# NFC_BusinessCard.net
KiCad netlist of a schematic drawn in EAGLE
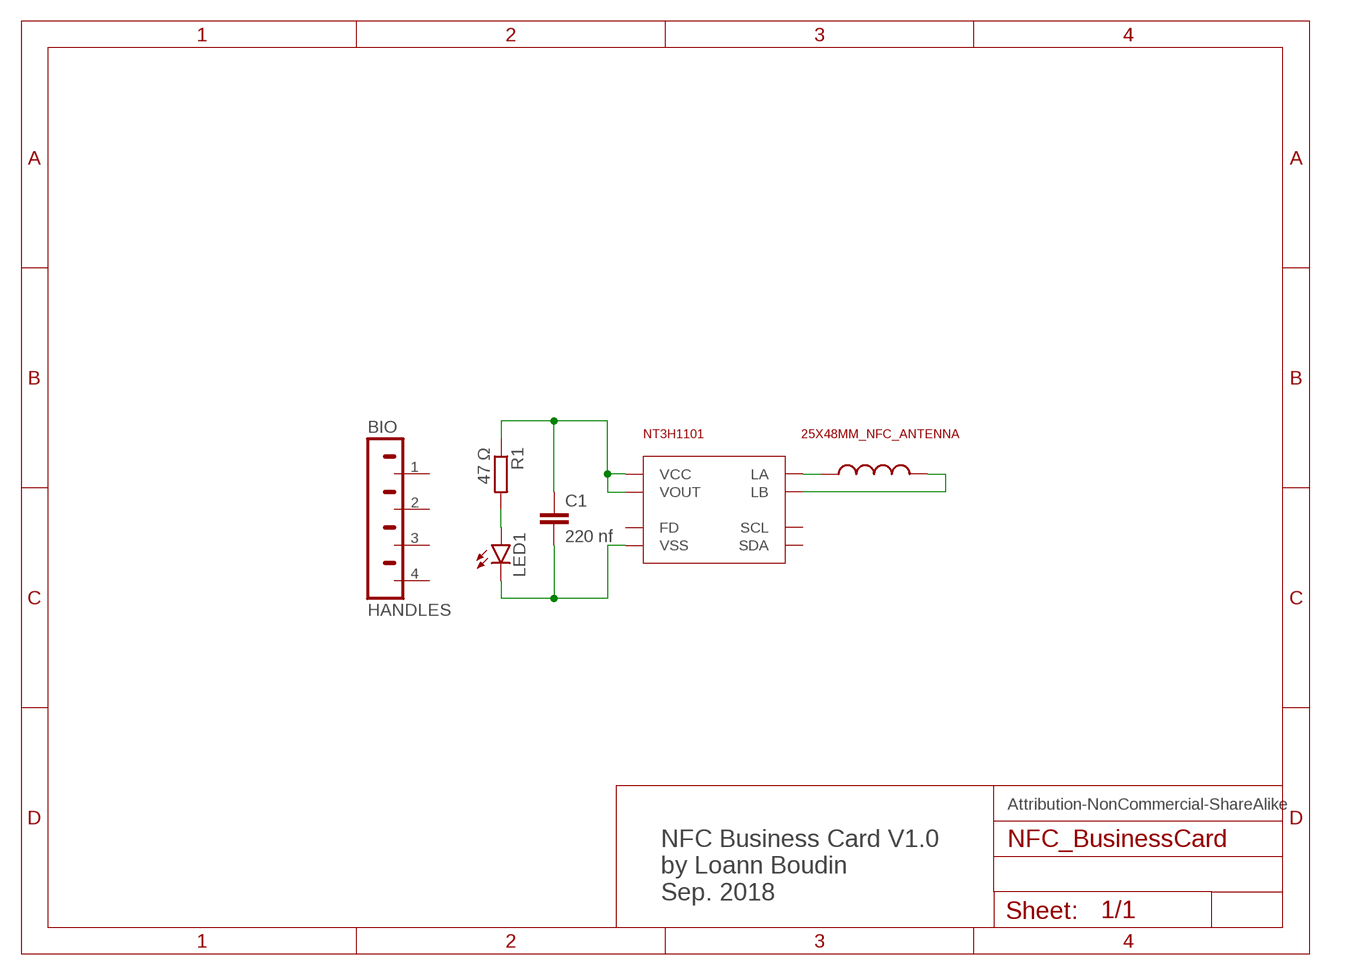
[diagram p0: schematic, sheet 1]

(export (version "E")
  (design (tool "Eeschema 10.0.6"))
  (components
    (comp (ref "ANT")
      (value "25X48MM_NFC_ANTENNA")
      (footprint "eagle-import:25X48MM_NFC")
      (libsource (lib "eagle-import") (part "25X48MM_NFC_ANTENNA"))
    )
    (comp (ref "BIO")
      (value "HANDLES")
      (footprint "eagle-import:MA08-1")
      (libsource (lib "eagle-import") (part "HANDLES"))
    )
    (comp (ref "C1")
      (value "220 nf")
      (footprint "eagle-import:C0603")
      (libsource (lib "eagle-import") (part "C-EUC0603"))
    )
    (comp (ref "LED1")
      (value "LEDSML0805")
      (footprint "eagle-import:SML0805")
      (libsource (lib "eagle-import") (part "LEDSML0805"))
    )
    (comp (ref "NT3H1101")
      (value "NT3H")
      (footprint "eagle-import:XQFN8")
      (libsource (lib "eagle-import") (part "NT3H"))
    )
    (comp (ref "R1")
      (value "47 Ω")
      (footprint "eagle-import:R0603")
      (libsource (lib "eagle-import") (part "R-EU_R0603"))
    )
  )
  (nets
    (net (code "1") (name "Net-(ANT-PadP$1)") (class "Default")
      (node (ref "ANT") (pin "P$1") (pinfunction "P$1_P$1") (pintype "bidirectional"))
      (node (ref "NT3H1101") (pin "LB") (pinfunction "LB_LB") (pintype "bidirectional"))
    )
    (net (code "2") (name "Net-(ANT-PadP$2)") (class "Default")
      (node (ref "ANT") (pin "P$2") (pinfunction "P$2_P$2") (pintype "bidirectional"))
      (node (ref "NT3H1101") (pin "LA") (pinfunction "LA_LA") (pintype "bidirectional"))
    )
    (net (code "3") (name "Net-(C1-Pad1)") (class "Default")
      (node (ref "C1") (pin "1") (pinfunction "1_1") (pintype "passive"))
      (node (ref "NT3H1101") (pin "VCC") (pinfunction "VCC_VCC") (pintype "bidirectional"))
      (node (ref "NT3H1101") (pin "VOUT") (pinfunction "VOUT_VOUT") (pintype "bidirectional"))
      (node (ref "R1") (pin "1") (pinfunction "1_1") (pintype "passive"))
    )
    (net (code "4") (name "Net-(C1-Pad2)") (class "Default")
      (node (ref "C1") (pin "2") (pinfunction "2_2") (pintype "passive"))
      (node (ref "LED1") (pin "C") (pinfunction "C_C") (pintype "passive"))
      (node (ref "NT3H1101") (pin "VSS") (pinfunction "VSS_VSS") (pintype "bidirectional"))
    )
    (net (code "5") (name "Net-(LED1-PadA)") (class "Default")
      (node (ref "LED1") (pin "A") (pinfunction "A_A") (pintype "passive"))
      (node (ref "R1") (pin "2") (pinfunction "2_2") (pintype "passive"))
    )
    (net (code "6") (name "unconnected-(BIO-1-Pad4)") (class "Default")
      (node (ref "BIO") (pin "4") (pinfunction "1_4") (pintype "passive"))
    )
    (net (code "7") (name "unconnected-(BIO-5-Pad2)") (class "Default")
      (node (ref "BIO") (pin "2") (pinfunction "5_2") (pintype "passive"))
    )
    (net (code "8") (name "unconnected-(BIO-7-Pad1)") (class "Default")
      (node (ref "BIO") (pin "1") (pinfunction "7_1") (pintype "passive"))
    )
    (net (code "9") (name "unconnected-(BIO-Pad3)") (class "Default")
      (node (ref "BIO") (pin "3") (pinfunction "3_3") (pintype "passive"))
    )
    (net (code "10") (name "unconnected-(NT3H1101-PadFD)") (class "Default")
      (node (ref "NT3H1101") (pin "FD") (pinfunction "FD_FD") (pintype "bidirectional"))
    )
    (net (code "11") (name "unconnected-(NT3H1101-PadSCL)") (class "Default")
      (node (ref "NT3H1101") (pin "SCL") (pinfunction "SCL_SCL") (pintype "bidirectional"))
    )
    (net (code "12") (name "unconnected-(NT3H1101-PadSDA)") (class "Default")
      (node (ref "NT3H1101") (pin "SDA") (pinfunction "SDA_SDA") (pintype "bidirectional"))
    )
  )
)
